# fuzz.net
KiCad netlist of a schematic drawn in EAGLE
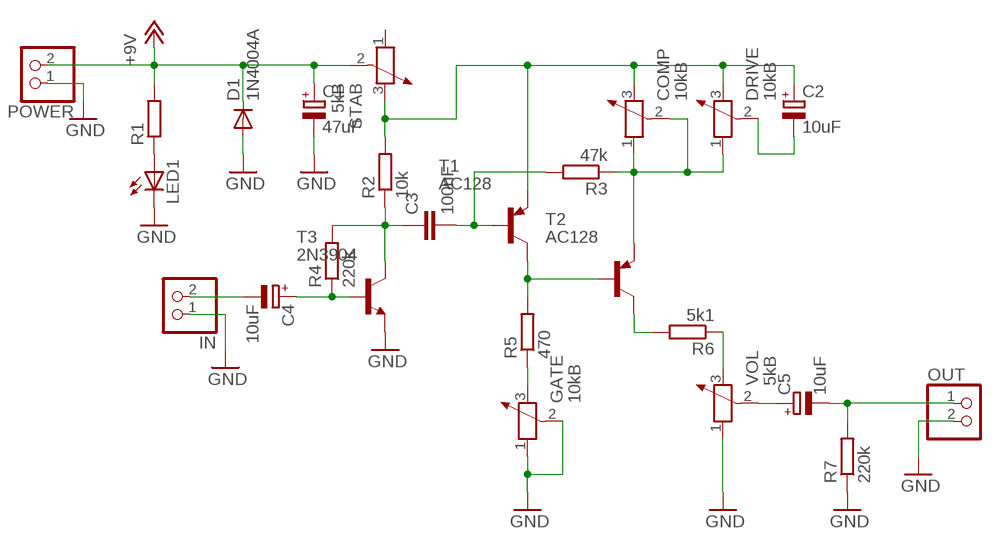
[diagram p0: schematic, sheet 1]

(export (version "E")
  (design (tool "Eeschema 10.0.6"))
  (components
    (comp (ref "C1")
      (value "47uF")
      (footprint "eagle-import:E2,5-6")
      (libsource (lib "eagle-import") (part "CPOL-EUE2.5-6"))
    )
    (comp (ref "C2")
      (value "10uF")
      (footprint "eagle-import:E2,5-6")
      (libsource (lib "eagle-import") (part "CPOL-EUE2.5-6"))
    )
    (comp (ref "C3")
      (value "100nF")
      (footprint "eagle-import:C050-045X075")
      (libsource (lib "eagle-import") (part "C-EU050-045X075"))
    )
    (comp (ref "C4")
      (value "10uF")
      (footprint "eagle-import:E2,5-6")
      (libsource (lib "eagle-import") (part "CPOL-EUE2.5-6"))
    )
    (comp (ref "C5")
      (value "10uF")
      (footprint "eagle-import:E2,5-6")
      (libsource (lib "eagle-import") (part "CPOL-EUE2.5-6"))
    )
    (comp (ref "COMP")
      (value "10kB")
      (footprint "eagle-import:1X03")
      (libsource (lib "eagle-import") (part "POTENTIOMETER_"))
    )
    (comp (ref "D1")
      (value "1N4004A")
      (footprint "eagle-import:DO41-5")
      (libsource (lib "eagle-import") (part "1N4004A"))
    )
    (comp (ref "DRIVE")
      (value "10kB")
      (footprint "eagle-import:1X03")
      (libsource (lib "eagle-import") (part "POTENTIOMETER_"))
    )
    (comp (ref "GATE")
      (value "10kB")
      (footprint "eagle-import:1X03")
      (libsource (lib "eagle-import") (part "POTENTIOMETER_"))
    )
    (comp (ref "IN")
      (value "PINHD-1X2")
      (footprint "eagle-import:1X02")
      (libsource (lib "eagle-import") (part "PINHD-1X2"))
    )
    (comp (ref "LED1")
      (value "LED3MM")
      (footprint "eagle-import:LED3MM")
      (libsource (lib "eagle-import") (part "LED3MM"))
    )
    (comp (ref "OUT")
      (value "PINHD-1X2")
      (footprint "eagle-import:1X02")
      (libsource (lib "eagle-import") (part "PINHD-1X2"))
    )
    (comp (ref "POWER")
      (value "PINHD-1X2")
      (footprint "eagle-import:1X02")
      (libsource (lib "eagle-import") (part "PINHD-1X2"))
    )
    (comp (ref "R1")
      (value "R-EU_")
      (footprint "eagle-import:R0805")
      (libsource (lib "eagle-import") (part "R-EU_"))
    )
    (comp (ref "R2")
      (value "10k")
      (footprint "eagle-import:0207_7")
      (libsource (lib "eagle-import") (part "R-EU_0207/7"))
    )
    (comp (ref "R3")
      (value "47k")
      (footprint "eagle-import:0207_7")
      (libsource (lib "eagle-import") (part "R-EU_0207/7"))
    )
    (comp (ref "R4")
      (value "220k")
      (footprint "eagle-import:0207_7")
      (libsource (lib "eagle-import") (part "R-EU_0207/7"))
    )
    (comp (ref "R5")
      (value "470")
      (footprint "eagle-import:0207_7")
      (libsource (lib "eagle-import") (part "R-EU_0207/7"))
    )
    (comp (ref "R6")
      (value "5k1")
      (footprint "eagle-import:0207_7")
      (libsource (lib "eagle-import") (part "R-EU_0207/7"))
    )
    (comp (ref "R7")
      (value "220k")
      (footprint "eagle-import:0207_7")
      (libsource (lib "eagle-import") (part "R-EU_0207/7"))
    )
    (comp (ref "STAB")
      (value "5kB")
      (footprint "eagle-import:1X03")
      (libsource (lib "eagle-import") (part "POTENTIOMETER_"))
    )
    (comp (ref "T1")
      (value "AC128")
      (footprint "eagle-import:TO18")
      (libsource (lib "eagle-import") (part "AC128"))
    )
    (comp (ref "T2")
      (value "AC128")
      (footprint "eagle-import:TO18")
      (libsource (lib "eagle-import") (part "AC128"))
    )
    (comp (ref "T3")
      (value "2N3904")
      (footprint "eagle-import:TO92")
      (libsource (lib "eagle-import") (part "2N3904"))
    )
    (comp (ref "VOL")
      (value "5kB")
      (footprint "eagle-import:1X03")
      (libsource (lib "eagle-import") (part "POTENTIOMETER_"))
    )
  )
  (nets
    (net (code "1") (name "+9V") (class "Default")
      (node (ref "C1") (pin "+") (pinfunction "+_+") (pintype "passive"))
      (node (ref "D1") (pin "C") (pinfunction "C_C") (pintype "passive"))
      (node (ref "POWER") (pin "2") (pinfunction "2_2") (pintype "passive"))
      (node (ref "R1") (pin "2") (pinfunction "2_2") (pintype "passive"))
      (node (ref "STAB") (pin "2") (pinfunction "3_2") (pintype "passive"))
    )
    (net (code "2") (name "GND") (class "Default")
      (node (ref "C1") (pin "-") (pinfunction "-_-") (pintype "passive"))
      (node (ref "D1") (pin "A") (pinfunction "A_A") (pintype "passive"))
      (node (ref "GATE") (pin "1") (pinfunction "1_1") (pintype "passive"))
      (node (ref "GATE") (pin "2") (pinfunction "3_2") (pintype "passive"))
      (node (ref "IN") (pin "1") (pinfunction "1_1") (pintype "passive"))
      (node (ref "LED1") (pin "K") (pinfunction "C_K") (pintype "passive"))
      (node (ref "OUT") (pin "2") (pinfunction "2_2") (pintype "passive"))
      (node (ref "POWER") (pin "1") (pinfunction "1_1") (pintype "passive"))
      (node (ref "R7") (pin "1") (pinfunction "1_1") (pintype "passive"))
      (node (ref "T3") (pin "3") (pinfunction "E_3") (pintype "passive"))
      (node (ref "VOL") (pin "1") (pinfunction "1_1") (pintype "passive"))
    )
    (net (code "3") (name "Net-(C4-Pad-)") (class "Default")
      (node (ref "C4") (pin "-") (pinfunction "-_-") (pintype "passive"))
      (node (ref "IN") (pin "2") (pinfunction "2_2") (pintype "passive"))
    )
    (net (code "4") (name "Net-(C5-Pad-)") (class "Default")
      (node (ref "C5") (pin "-") (pinfunction "-_-") (pintype "passive"))
      (node (ref "OUT") (pin "1") (pinfunction "1_1") (pintype "passive"))
      (node (ref "R7") (pin "2") (pinfunction "2_2") (pintype "passive"))
    )
    (net (code "5") (name "Net-(COMP-2)") (class "Default")
      (node (ref "C2") (pin "+") (pinfunction "+_+") (pintype "passive"))
      (node (ref "COMP") (pin "3") (pinfunction "2_3") (pintype "passive"))
      (node (ref "DRIVE") (pin "3") (pinfunction "2_3") (pintype "passive"))
      (node (ref "R2") (pin "2") (pinfunction "2_2") (pintype "passive"))
      (node (ref "STAB") (pin "3") (pinfunction "2_3") (pintype "passive"))
      (node (ref "T1") (pin "1") (pinfunction "E_1") (pintype "passive"))
    )
    (net (code "6") (name "Net-(COMP-3)") (class "Default")
      (node (ref "COMP") (pin "1") (pinfunction "1_1") (pintype "passive"))
      (node (ref "COMP") (pin "2") (pinfunction "3_2") (pintype "passive"))
      (node (ref "DRIVE") (pin "1") (pinfunction "1_1") (pintype "passive"))
      (node (ref "R3") (pin "1") (pinfunction "1_1") (pintype "passive"))
      (node (ref "T2") (pin "1") (pinfunction "E_1") (pintype "passive"))
    )
    (net (code "7") (name "Net-(DRIVE-3)") (class "Default")
      (node (ref "C2") (pin "-") (pinfunction "-_-") (pintype "passive"))
      (node (ref "DRIVE") (pin "2") (pinfunction "3_2") (pintype "passive"))
    )
    (net (code "8") (name "Net-(GATE-2)") (class "Default")
      (node (ref "GATE") (pin "3") (pinfunction "2_3") (pintype "passive"))
      (node (ref "R5") (pin "1") (pinfunction "1_1") (pintype "passive"))
    )
    (net (code "9") (name "Net-(LED1-PadA)") (class "Default")
      (node (ref "LED1") (pin "A") (pinfunction "A_A") (pintype "passive"))
      (node (ref "R1") (pin "1") (pinfunction "1_1") (pintype "passive"))
    )
    (net (code "10") (name "Net-(T1-B)") (class "Default")
      (node (ref "C3") (pin "2") (pinfunction "2_2") (pintype "passive"))
      (node (ref "R3") (pin "2") (pinfunction "2_2") (pintype "passive"))
      (node (ref "T1") (pin "2") (pinfunction "B_2") (pintype "passive"))
    )
    (net (code "11") (name "Net-(T1-C)") (class "Default")
      (node (ref "R5") (pin "2") (pinfunction "2_2") (pintype "passive"))
      (node (ref "T1") (pin "3") (pinfunction "C_3") (pintype "passive"))
      (node (ref "T2") (pin "2") (pinfunction "B_2") (pintype "passive"))
    )
    (net (code "12") (name "Net-(T2-C)") (class "Default")
      (node (ref "R6") (pin "2") (pinfunction "2_2") (pintype "passive"))
      (node (ref "T2") (pin "3") (pinfunction "C_3") (pintype "passive"))
    )
    (net (code "13") (name "Net-(T3-B)") (class "Default")
      (node (ref "C4") (pin "+") (pinfunction "+_+") (pintype "passive"))
      (node (ref "R4") (pin "1") (pinfunction "1_1") (pintype "passive"))
      (node (ref "T3") (pin "2") (pinfunction "B_2") (pintype "passive"))
    )
    (net (code "14") (name "Net-(T3-C)") (class "Default")
      (node (ref "C3") (pin "1") (pinfunction "1_1") (pintype "passive"))
      (node (ref "R2") (pin "1") (pinfunction "1_1") (pintype "passive"))
      (node (ref "R4") (pin "2") (pinfunction "2_2") (pintype "passive"))
      (node (ref "T3") (pin "1") (pinfunction "C_1") (pintype "passive"))
    )
    (net (code "15") (name "Net-(VOL-2)") (class "Default")
      (node (ref "R6") (pin "1") (pinfunction "1_1") (pintype "passive"))
      (node (ref "VOL") (pin "3") (pinfunction "2_3") (pintype "passive"))
    )
    (net (code "16") (name "Net-(VOL-3)") (class "Default")
      (node (ref "C5") (pin "+") (pinfunction "+_+") (pintype "passive"))
      (node (ref "VOL") (pin "2") (pinfunction "3_2") (pintype "passive"))
    )
    (net (code "17") (name "unconnected-(STAB-Pad1)") (class "Default")
      (node (ref "STAB") (pin "1") (pinfunction "1_1") (pintype "passive"))
    )
  )
)
